# master.net
KiCad netlist of a schematic drawn in EAGLE
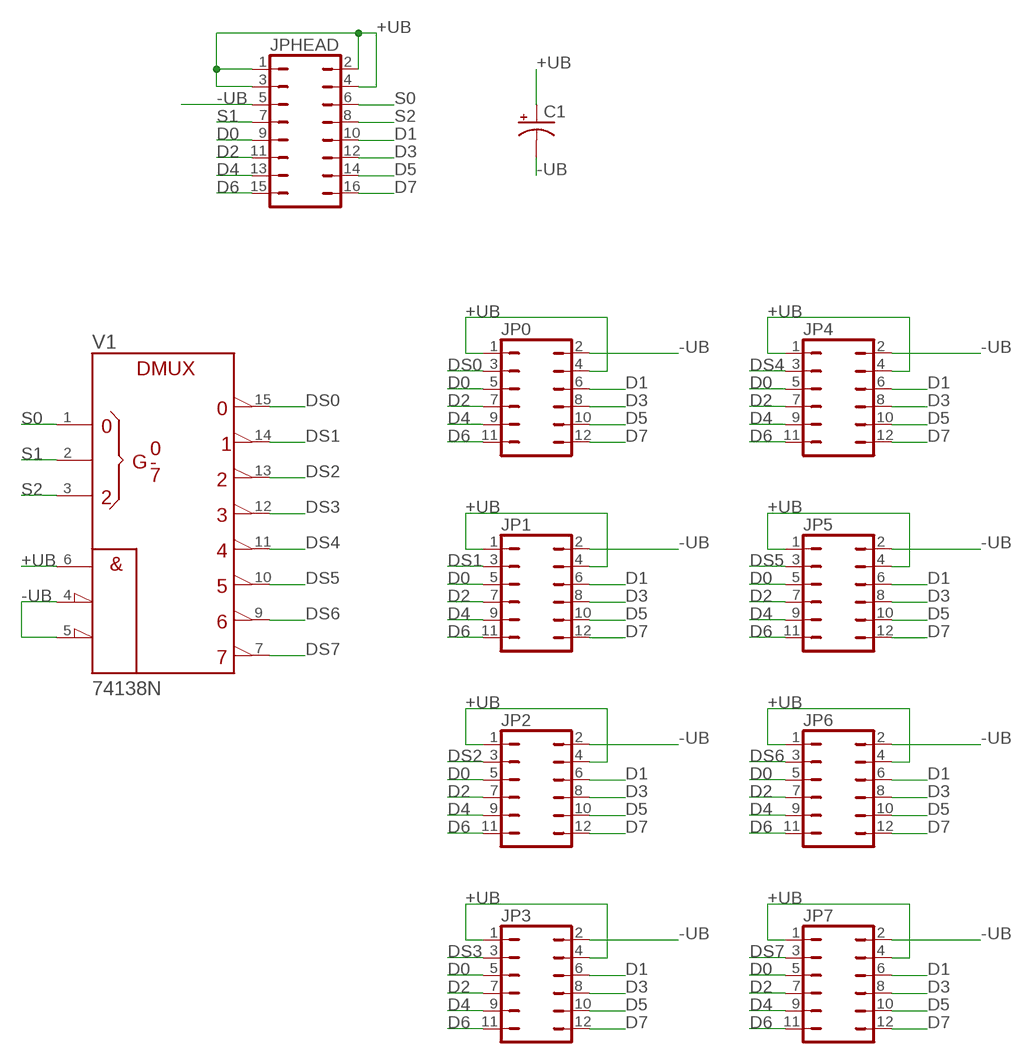
[diagram p0: schematic, sheet 1]

(export (version "E")
  (design (tool "Eeschema 10.0.6"))
  (components
    (comp (ref "C1")
      (value "CPOL-USTT2D4")
      (footprint "eagle-import:TT2D4")
      (libsource (lib "eagle-import") (part "CPOL-USTT2D4"))
    )
    (comp (ref "JP0")
      (value "JP6Q")
      (footprint "eagle-import:JP6Q")
      (libsource (lib "eagle-import") (part "JP6Q"))
    )
    (comp (ref "JP1")
      (value "JP6Q")
      (footprint "eagle-import:JP6Q")
      (libsource (lib "eagle-import") (part "JP6Q"))
    )
    (comp (ref "JP2")
      (value "JP6Q")
      (footprint "eagle-import:JP6Q")
      (libsource (lib "eagle-import") (part "JP6Q"))
    )
    (comp (ref "JP3")
      (value "JP6Q")
      (footprint "eagle-import:JP6Q")
      (libsource (lib "eagle-import") (part "JP6Q"))
    )
    (comp (ref "JP4")
      (value "JP6Q")
      (footprint "eagle-import:JP6Q")
      (libsource (lib "eagle-import") (part "JP6Q"))
    )
    (comp (ref "JP5")
      (value "JP6Q")
      (footprint "eagle-import:JP6Q")
      (libsource (lib "eagle-import") (part "JP6Q"))
    )
    (comp (ref "JP6")
      (value "JP6Q")
      (footprint "eagle-import:JP6Q")
      (libsource (lib "eagle-import") (part "JP6Q"))
    )
    (comp (ref "JP7")
      (value "JP6Q")
      (footprint "eagle-import:JP6Q")
      (libsource (lib "eagle-import") (part "JP6Q"))
    )
    (comp (ref "JPHEAD")
      (value "JP8Q")
      (footprint "eagle-import:JP8Q")
      (libsource (lib "eagle-import") (part "JP8Q"))
    )
    (comp (ref "V1")
      (value "74138N")
      (footprint "eagle-import:DIL16")
      (libsource (lib "eagle-import") (part "74138N"))
    )
  )
  (nets
    (net (code "1") (name "/+UB") (class "Default")
      (node (ref "C1") (pin "+") (pinfunction "+_+") (pintype "passive"))
      (node (ref "JP0") (pin "1") (pinfunction "1_1") (pintype "passive"))
      (node (ref "JP0") (pin "4") (pinfunction "4_4") (pintype "passive"))
      (node (ref "JP1") (pin "1") (pinfunction "1_1") (pintype "passive"))
      (node (ref "JP1") (pin "4") (pinfunction "4_4") (pintype "passive"))
      (node (ref "JP2") (pin "1") (pinfunction "1_1") (pintype "passive"))
      (node (ref "JP2") (pin "4") (pinfunction "4_4") (pintype "passive"))
      (node (ref "JP3") (pin "1") (pinfunction "1_1") (pintype "passive"))
      (node (ref "JP3") (pin "4") (pinfunction "4_4") (pintype "passive"))
      (node (ref "JP4") (pin "1") (pinfunction "1_1") (pintype "passive"))
      (node (ref "JP4") (pin "4") (pinfunction "4_4") (pintype "passive"))
      (node (ref "JP5") (pin "1") (pinfunction "1_1") (pintype "passive"))
      (node (ref "JP5") (pin "4") (pinfunction "4_4") (pintype "passive"))
      (node (ref "JP6") (pin "1") (pinfunction "1_1") (pintype "passive"))
      (node (ref "JP6") (pin "4") (pinfunction "4_4") (pintype "passive"))
      (node (ref "JP7") (pin "1") (pinfunction "1_1") (pintype "passive"))
      (node (ref "JP7") (pin "4") (pinfunction "4_4") (pintype "passive"))
      (node (ref "JPHEAD") (pin "1") (pinfunction "1_1") (pintype "passive"))
      (node (ref "JPHEAD") (pin "2") (pinfunction "2_2") (pintype "passive"))
      (node (ref "JPHEAD") (pin "3") (pinfunction "3_3") (pintype "passive"))
      (node (ref "JPHEAD") (pin "4") (pinfunction "4_4") (pintype "passive"))
      (node (ref "V1") (pin "6") (pinfunction "G1_6") (pintype "input"))
    )
    (net (code "2") (name "/-UB") (class "Default")
      (node (ref "C1") (pin "-") (pinfunction "-_-") (pintype "passive"))
      (node (ref "JP0") (pin "2") (pinfunction "2_2") (pintype "passive"))
      (node (ref "JP1") (pin "2") (pinfunction "2_2") (pintype "passive"))
      (node (ref "JP2") (pin "2") (pinfunction "2_2") (pintype "passive"))
      (node (ref "JP3") (pin "2") (pinfunction "2_2") (pintype "passive"))
      (node (ref "JP4") (pin "2") (pinfunction "2_2") (pintype "passive"))
      (node (ref "JP5") (pin "2") (pinfunction "2_2") (pintype "passive"))
      (node (ref "JP6") (pin "2") (pinfunction "2_2") (pintype "passive"))
      (node (ref "JP7") (pin "2") (pinfunction "2_2") (pintype "passive"))
      (node (ref "JPHEAD") (pin "5") (pinfunction "5_5") (pintype "passive"))
      (node (ref "V1") (pin "4") (pinfunction "~{G2A}_4") (pintype "input"))
      (node (ref "V1") (pin "5") (pinfunction "~{G2B}_5") (pintype "input"))
    )
    (net (code "3") (name "/D0") (class "Default")
      (node (ref "JP0") (pin "5") (pinfunction "5_5") (pintype "passive"))
      (node (ref "JP1") (pin "5") (pinfunction "5_5") (pintype "passive"))
      (node (ref "JP2") (pin "5") (pinfunction "5_5") (pintype "passive"))
      (node (ref "JP3") (pin "5") (pinfunction "5_5") (pintype "passive"))
      (node (ref "JP4") (pin "5") (pinfunction "5_5") (pintype "passive"))
      (node (ref "JP5") (pin "5") (pinfunction "5_5") (pintype "passive"))
      (node (ref "JP6") (pin "5") (pinfunction "5_5") (pintype "passive"))
      (node (ref "JP7") (pin "5") (pinfunction "5_5") (pintype "passive"))
      (node (ref "JPHEAD") (pin "9") (pinfunction "9_9") (pintype "passive"))
    )
    (net (code "4") (name "/D1") (class "Default")
      (node (ref "JP0") (pin "6") (pinfunction "6_6") (pintype "passive"))
      (node (ref "JP1") (pin "6") (pinfunction "6_6") (pintype "passive"))
      (node (ref "JP2") (pin "6") (pinfunction "6_6") (pintype "passive"))
      (node (ref "JP3") (pin "6") (pinfunction "6_6") (pintype "passive"))
      (node (ref "JP4") (pin "6") (pinfunction "6_6") (pintype "passive"))
      (node (ref "JP5") (pin "6") (pinfunction "6_6") (pintype "passive"))
      (node (ref "JP6") (pin "6") (pinfunction "6_6") (pintype "passive"))
      (node (ref "JP7") (pin "6") (pinfunction "6_6") (pintype "passive"))
      (node (ref "JPHEAD") (pin "10") (pinfunction "10_10") (pintype "passive"))
    )
    (net (code "5") (name "/D2") (class "Default")
      (node (ref "JP0") (pin "7") (pinfunction "7_7") (pintype "passive"))
      (node (ref "JP1") (pin "7") (pinfunction "7_7") (pintype "passive"))
      (node (ref "JP2") (pin "7") (pinfunction "7_7") (pintype "passive"))
      (node (ref "JP3") (pin "7") (pinfunction "7_7") (pintype "passive"))
      (node (ref "JP4") (pin "7") (pinfunction "7_7") (pintype "passive"))
      (node (ref "JP5") (pin "7") (pinfunction "7_7") (pintype "passive"))
      (node (ref "JP6") (pin "7") (pinfunction "7_7") (pintype "passive"))
      (node (ref "JP7") (pin "7") (pinfunction "7_7") (pintype "passive"))
      (node (ref "JPHEAD") (pin "11") (pinfunction "11_11") (pintype "passive"))
    )
    (net (code "6") (name "/D3") (class "Default")
      (node (ref "JP0") (pin "8") (pinfunction "8_8") (pintype "passive"))
      (node (ref "JP1") (pin "8") (pinfunction "8_8") (pintype "passive"))
      (node (ref "JP2") (pin "8") (pinfunction "8_8") (pintype "passive"))
      (node (ref "JP3") (pin "8") (pinfunction "8_8") (pintype "passive"))
      (node (ref "JP4") (pin "8") (pinfunction "8_8") (pintype "passive"))
      (node (ref "JP5") (pin "8") (pinfunction "8_8") (pintype "passive"))
      (node (ref "JP6") (pin "8") (pinfunction "8_8") (pintype "passive"))
      (node (ref "JP7") (pin "8") (pinfunction "8_8") (pintype "passive"))
      (node (ref "JPHEAD") (pin "12") (pinfunction "12_12") (pintype "passive"))
    )
    (net (code "7") (name "/D4") (class "Default")
      (node (ref "JP0") (pin "9") (pinfunction "9_9") (pintype "passive"))
      (node (ref "JP1") (pin "9") (pinfunction "9_9") (pintype "passive"))
      (node (ref "JP2") (pin "9") (pinfunction "9_9") (pintype "passive"))
      (node (ref "JP3") (pin "9") (pinfunction "9_9") (pintype "passive"))
      (node (ref "JP4") (pin "9") (pinfunction "9_9") (pintype "passive"))
      (node (ref "JP5") (pin "9") (pinfunction "9_9") (pintype "passive"))
      (node (ref "JP6") (pin "9") (pinfunction "9_9") (pintype "passive"))
      (node (ref "JP7") (pin "9") (pinfunction "9_9") (pintype "passive"))
      (node (ref "JPHEAD") (pin "13") (pinfunction "13_13") (pintype "passive"))
    )
    (net (code "8") (name "/D5") (class "Default")
      (node (ref "JP0") (pin "10") (pinfunction "10_10") (pintype "passive"))
      (node (ref "JP1") (pin "10") (pinfunction "10_10") (pintype "passive"))
      (node (ref "JP2") (pin "10") (pinfunction "10_10") (pintype "passive"))
      (node (ref "JP3") (pin "10") (pinfunction "10_10") (pintype "passive"))
      (node (ref "JP4") (pin "10") (pinfunction "10_10") (pintype "passive"))
      (node (ref "JP5") (pin "10") (pinfunction "10_10") (pintype "passive"))
      (node (ref "JP6") (pin "10") (pinfunction "10_10") (pintype "passive"))
      (node (ref "JP7") (pin "10") (pinfunction "10_10") (pintype "passive"))
      (node (ref "JPHEAD") (pin "14") (pinfunction "14_14") (pintype "passive"))
    )
    (net (code "9") (name "/D6") (class "Default")
      (node (ref "JP0") (pin "11") (pinfunction "11_11") (pintype "passive"))
      (node (ref "JP1") (pin "11") (pinfunction "11_11") (pintype "passive"))
      (node (ref "JP2") (pin "11") (pinfunction "11_11") (pintype "passive"))
      (node (ref "JP3") (pin "11") (pinfunction "11_11") (pintype "passive"))
      (node (ref "JP4") (pin "11") (pinfunction "11_11") (pintype "passive"))
      (node (ref "JP5") (pin "11") (pinfunction "11_11") (pintype "passive"))
      (node (ref "JP6") (pin "11") (pinfunction "11_11") (pintype "passive"))
      (node (ref "JP7") (pin "11") (pinfunction "11_11") (pintype "passive"))
      (node (ref "JPHEAD") (pin "15") (pinfunction "15_15") (pintype "passive"))
    )
    (net (code "10") (name "/D7") (class "Default")
      (node (ref "JP0") (pin "12") (pinfunction "12_12") (pintype "passive"))
      (node (ref "JP1") (pin "12") (pinfunction "12_12") (pintype "passive"))
      (node (ref "JP2") (pin "12") (pinfunction "12_12") (pintype "passive"))
      (node (ref "JP3") (pin "12") (pinfunction "12_12") (pintype "passive"))
      (node (ref "JP4") (pin "12") (pinfunction "12_12") (pintype "passive"))
      (node (ref "JP5") (pin "12") (pinfunction "12_12") (pintype "passive"))
      (node (ref "JP6") (pin "12") (pinfunction "12_12") (pintype "passive"))
      (node (ref "JP7") (pin "12") (pinfunction "12_12") (pintype "passive"))
      (node (ref "JPHEAD") (pin "16") (pinfunction "16_16") (pintype "passive"))
    )
    (net (code "11") (name "/DS0") (class "Default")
      (node (ref "JP0") (pin "3") (pinfunction "3_3") (pintype "passive"))
      (node (ref "V1") (pin "15") (pinfunction "Y0_15") (pintype "output"))
    )
    (net (code "12") (name "/DS1") (class "Default")
      (node (ref "JP1") (pin "3") (pinfunction "3_3") (pintype "passive"))
      (node (ref "V1") (pin "14") (pinfunction "Y1_14") (pintype "output"))
    )
    (net (code "13") (name "/DS2") (class "Default")
      (node (ref "JP2") (pin "3") (pinfunction "3_3") (pintype "passive"))
      (node (ref "V1") (pin "13") (pinfunction "Y2_13") (pintype "output"))
    )
    (net (code "14") (name "/DS3") (class "Default")
      (node (ref "JP3") (pin "3") (pinfunction "3_3") (pintype "passive"))
      (node (ref "V1") (pin "12") (pinfunction "Y3_12") (pintype "output"))
    )
    (net (code "15") (name "/DS4") (class "Default")
      (node (ref "JP4") (pin "3") (pinfunction "3_3") (pintype "passive"))
      (node (ref "V1") (pin "11") (pinfunction "Y4_11") (pintype "output"))
    )
    (net (code "16") (name "/DS5") (class "Default")
      (node (ref "JP5") (pin "3") (pinfunction "3_3") (pintype "passive"))
      (node (ref "V1") (pin "10") (pinfunction "Y5_10") (pintype "output"))
    )
    (net (code "17") (name "/DS6") (class "Default")
      (node (ref "JP6") (pin "3") (pinfunction "3_3") (pintype "passive"))
      (node (ref "V1") (pin "9") (pinfunction "Y6_9") (pintype "output"))
    )
    (net (code "18") (name "/DS7") (class "Default")
      (node (ref "JP7") (pin "3") (pinfunction "3_3") (pintype "passive"))
      (node (ref "V1") (pin "7") (pinfunction "Y7_7") (pintype "output"))
    )
    (net (code "19") (name "/S0") (class "Default")
      (node (ref "JPHEAD") (pin "6") (pinfunction "6_6") (pintype "passive"))
      (node (ref "V1") (pin "1") (pinfunction "A_1") (pintype "input"))
    )
    (net (code "20") (name "/S1") (class "Default")
      (node (ref "JPHEAD") (pin "7") (pinfunction "7_7") (pintype "passive"))
      (node (ref "V1") (pin "2") (pinfunction "B_2") (pintype "input"))
    )
    (net (code "21") (name "/S2") (class "Default")
      (node (ref "JPHEAD") (pin "8") (pinfunction "8_8") (pintype "passive"))
      (node (ref "V1") (pin "3") (pinfunction "C_3") (pintype "input"))
    )
  )
)
